# NRF52.net
KiCad netlist of a schematic drawn in Altium Designer
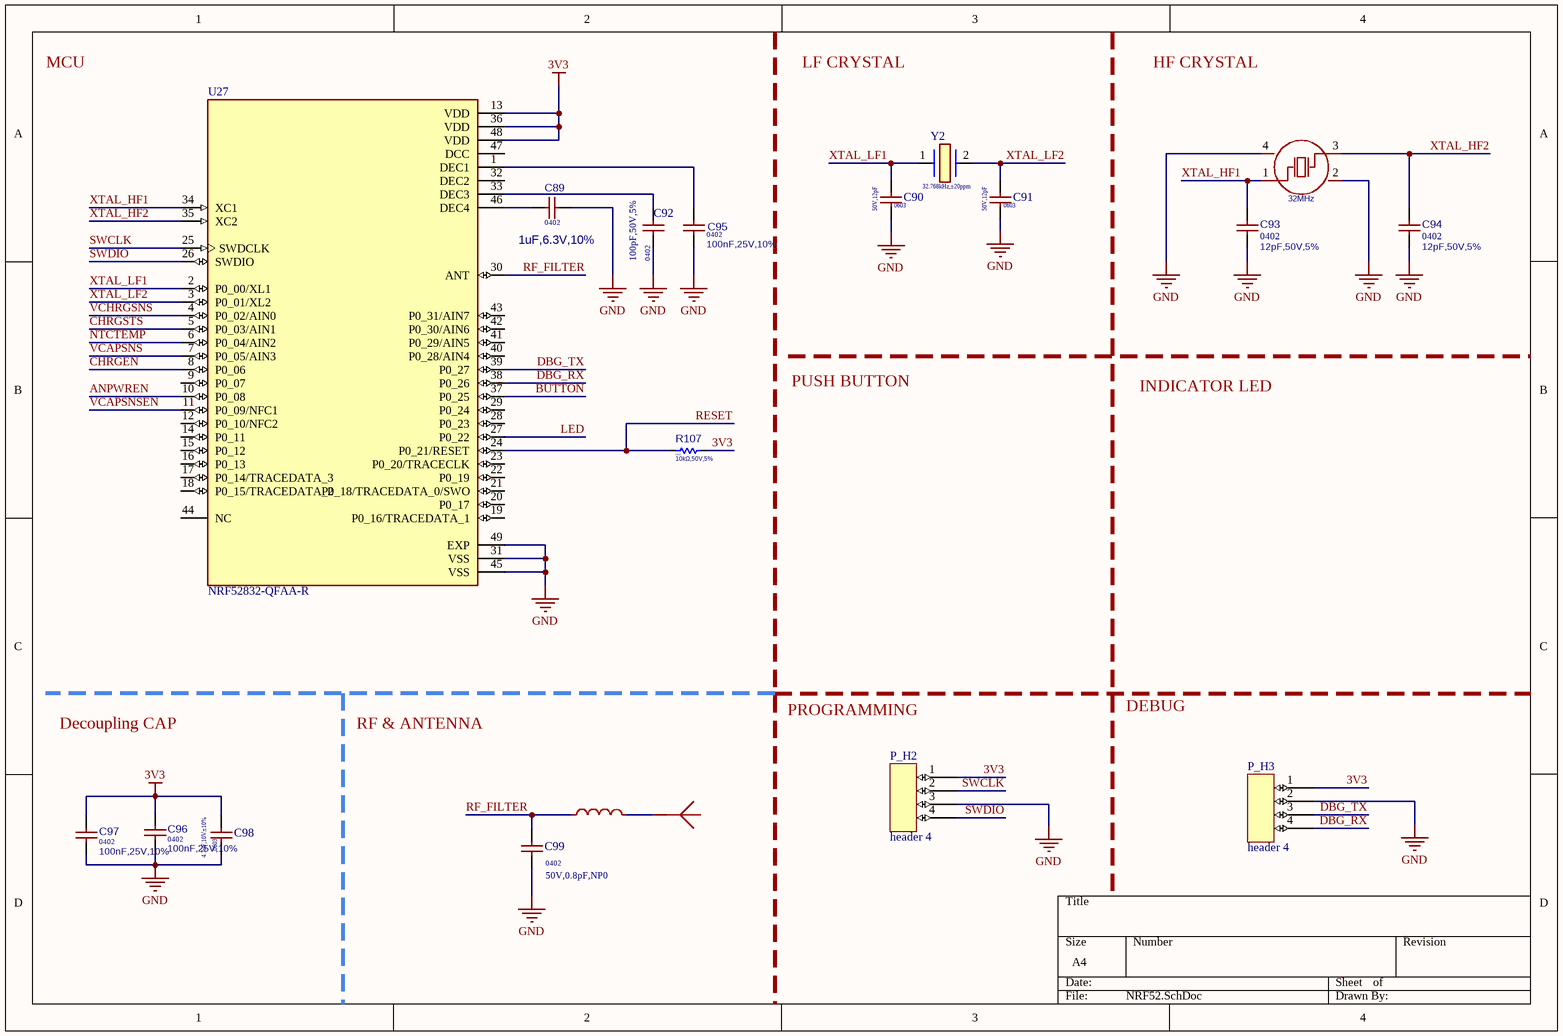
[diagram p0: NRF52.SchDoc]

(export (version "E")
  (design (tool "Eeschema 10.0.6"))
  (components
    (comp (ref "AE1")
      (value "2450AT18A100E")
      (footprint "ANT 1206")
      (description "0.5dBi 2.4G Antenna 2.4GHz 2W 1206 Antennas ROHS")
      (fields (field (name "MANUFACTURER") "JOHANSON"))
      (libsource (lib "RCL") (part "2450AT18A100E"))
    )
    (comp (ref "C89")
      (value "1uF,6.3V,10%")
      (footprint "C0402")
      (description "6.3V 1uF X7R ±10% 0402 Multilayer Ceramic Capacitors MLCC - SMD/SMT ROHS")
      (fields
        (field (name "MANUFACTURER") "YAGEO")
        (field (name "MPN") "CC0402KRX7R5BB105")
        (field (name "PACKAGE") "0402")
      )
      (libsource (lib "RCL") (part "CC0402KRX7R5BB105"))
    )
    (comp (ref "C90")
      (value "50V,12pF")
      (footprint "CAPC1608X90N")
      (description "50V 12pF C0G ±5% 0603 Multilayer Ceramic Capacitors MLCC - SMD/SMT ROHS")
      (fields
        (field (name "MANUFACTURER") "FH")
        (field (name "MPN") "0603CG120J500NT")
        (field (name "PACKAGE") "0603")
      )
      (libsource (lib "RCL") (part "0603CG120J500NT"))
    )
    (comp (ref "C91")
      (value "50V,12pF")
      (footprint "CAPC1608X90N")
      (description "50V 12pF C0G ±5% 0603 Multilayer Ceramic Capacitors MLCC - SMD/SMT ROHS")
      (fields
        (field (name "MANUFACTURER") "FH")
        (field (name "MPN") "0603CG120J500NT")
        (field (name "PACKAGE") "0603")
      )
      (libsource (lib "RCL") (part "0603CG120J500NT"))
    )
    (comp (ref "C92")
      (value "100pF,50V,5%")
      (footprint "C0402")
      (description "50V 100pF NP0 ±5% 0402 Multilayer Ceramic Capacitors MLCC - SMD/SMT ROHS")
      (fields
        (field (name "MANUFACTURER") "YAGEO")
        (field (name "MPN") "CC0402JRNPO9BN101")
        (field (name "PACKAGE") "0402")
      )
      (libsource (lib "RCL") (part "CC0402JRNPO9BN101"))
    )
    (comp (ref "C93")
      (value "12pF,50V,5%")
      (footprint "C0402")
      (description "12 pF ±5% 50V Ceramic Capacitor C0G, NP0 0402 (1005 Metric)")
      (fields
        (field (name "MANUFACTURER") "SAMSUNG")
        (field (name "MPN") "CL05C120JB51PNC")
        (field (name "PACKAGE") "0402")
      )
      (libsource (lib "RCL") (part "CL05C120JB51PNC"))
    )
    (comp (ref "C94")
      (value "12pF,50V,5%")
      (footprint "C0402")
      (description "12 pF ±5% 50V Ceramic Capacitor C0G, NP0 0402 (1005 Metric)")
      (fields
        (field (name "MANUFACTURER") "SAMSUNG")
        (field (name "MPN") "CL05C120JB51PNC")
        (field (name "PACKAGE") "0402")
      )
      (libsource (lib "RCL") (part "CL05C120JB51PNC"))
    )
    (comp (ref "C95")
      (value "100nF,25V,10%")
      (footprint "C0402")
      (description "25V 100nF X5R ±10% 0402 Multilayer Ceramic Capacitors MLCC - SMD/SMT ROHS")
      (fields
        (field (name "MANUFACTURER") "SAMSUNG")
        (field (name "MPN") "CL05A104KA5NNNC")
        (field (name "PACKAGE") "0402")
      )
      (libsource (lib "RCL") (part "CL05A104KA5NNNC"))
    )
    (comp (ref "C96")
      (value "100nF,25V,10%")
      (footprint "C0402")
      (description "25V 100nF X5R ±10% 0402 Multilayer Ceramic Capacitors MLCC - SMD/SMT ROHS")
      (fields
        (field (name "MANUFACTURER") "SAMSUNG")
        (field (name "MPN") "CL05A104KA5NNNC")
        (field (name "PACKAGE") "0402")
      )
      (libsource (lib "RCL") (part "CL05A104KA5NNNC"))
    )
    (comp (ref "C97")
      (value "100nF,25V,10%")
      (footprint "C0402")
      (description "25V 100nF X5R ±10% 0402 Multilayer Ceramic Capacitors MLCC - SMD/SMT ROHS")
      (fields
        (field (name "MANUFACTURER") "SAMSUNG")
        (field (name "MPN") "CL05A104KA5NNNC")
        (field (name "PACKAGE") "0402")
      )
      (libsource (lib "RCL") (part "CL05A104KA5NNNC"))
    )
    (comp (ref "C98")
      (value "4.7uF,10V±10%")
      (footprint "C0603")
      (description "10V 4.7uF X7R ±10% 0603 Multilayer Ceramic Capacitors MLCC - SMD/SMT ROHS")
      (fields
        (field (name "MPN") "CL10A475KQ8NNNC")
        (field (name "MANUFACTURER") "Samsung Electro-Mechanics")
        (field (name "PACKAGE") "0603")
      )
      (libsource (lib "RCL") (part "0603B475K100NT"))
    )
    (comp (ref "C99")
      (value "50V,0.8pF,NP0")
      (footprint "C0402")
      (description "50V 0.8pF NP0 0402 Multilayer Ceramic Capacitors MLCC - SMD/SMT ROHS")
      (fields
        (field (name "MANUFACTURER") "Walsin Tech Corp")
        (field (name "MPN") "RF15N0R8A500")
        (field (name "PACKAGE") "0402")
      )
      (libsource (lib "RCL") (part "RF15N0R8A500"))
    )
    (comp (ref "L4")
      (value "3.9nH")
      (footprint "L-0402")
      (description "300mA 3.9nH 200mΩ 0402 Inductors (SMD) ROHS")
      (fields (field (name "MANUFACTURER") "Sunlord") (field (name "MPN") "SDCL1005C3N9STDF"))
      (libsource (lib "RCL") (part "SDCL1005C3N9STDF"))
    )
    (comp (ref "P_H2")
      (value "header 4")
      (footprint "pin header 4")
      (description "Straight 2.54mm 6mm -40℃~+105℃ 1 3mm 4 2.54mm Black Brass 1x4P Straight,P=2.54mm Pin Headers ROHS")
      (libsource (lib "connector_button") (part "header 4"))
    )
    (comp (ref "P_H3")
      (value "header 4")
      (footprint "pin header 4")
      (description "Straight 2.54mm 6mm -40℃~+105℃ 1 3mm 4 2.54mm Black Brass 1x4P Straight,P=2.54mm Pin Headers ROHS")
      (libsource (lib "connector_button") (part "header 4"))
    )
    (comp (ref "R107")
      (value "10kΩ,50V,5%")
      (footprint "R0402")
      (description "62.5mW Thick Film Resistors 50V ±100ppm/℃ ±5% 10kΩ 0402 Chip Resistor - Surface Mount ROHS")
      (fields
        (field (name "MANUFACTURER") "YAGEO")
        (field (name "MPN") "RC0402JR-0710KL")
        (field (name "PACKAGE") "0402")
      )
      (libsource (lib "RCL") (part "RC0402JR-0710KL"))
    )
    (comp (ref "U27")
      (value "NRF52832-QFAA-R")
      (footprint "QFN40P600X600X90-49N")
      (description "IC RF TxRx + MCU Bluetooth, General ISM > 1GHz ANT, Bluetooth v5.0 2.4GHz 48-VFQFN Exposed Pad")
      (fields (field (name "MANUFACTURER") "Nordic"))
      (libsource (lib "IC") (part "NRF52832-QFAA-R"))
    )
    (comp (ref "X3")
      (value "32MHz")
      (footprint "SMD2016-4P,crystral")
      (description "32MHz,SMD2016-4P Crystals ROHS")
      (fields (field (name "MANUFACTURER") "HELE") (field (name "MPN") "X2C032000B81H-HS"))
      (libsource (lib "RCL") (part "X2C032000B81H-HS"))
    )
    (comp (ref "Y2")
      (value "32.768kHz,±20ppm")
      (footprint "SMD3215-2P")
      (description "32.768kHz SMD Crystal Resonator 12.5pF 70kΩ ±20ppm -40℃~+85℃ SMD3215-2P Crystals ROHS")
      (fields (field (name "MANUFACTURER") "Seiko Epson") (field (name "MPN") "Q13FC1350000400"))
      (libsource (lib "RCL") (part "Q13FC1350000400"))
    )
  )
  (nets
    (net (code "1") (name "/ANPWREN") (class "Default")
      (node (ref "U27") (pin "10") (pinfunction "P0_08_10") (pintype "bidirectional"))
    )
    (net (code "2") (name "/BUTTON") (class "Default")
      (node (ref "U27") (pin "37") (pinfunction "P0_25_37") (pintype "bidirectional"))
    )
    (net (code "3") (name "/CHRGEN") (class "Default")
      (node (ref "U27") (pin "8") (pinfunction "P0_06_8") (pintype "bidirectional"))
    )
    (net (code "4") (name "/CHRGSTS") (class "Default")
      (node (ref "U27") (pin "5") (pinfunction "P0_03/AIN1_5") (pintype "bidirectional"))
    )
    (net (code "5") (name "/DBG_RX") (class "Default")
      (node (ref "P_H3") (pin "4") (pintype "bidirectional"))
      (node (ref "U27") (pin "38") (pinfunction "P0_26_38") (pintype "bidirectional"))
    )
    (net (code "6") (name "/DBG_TX") (class "Default")
      (node (ref "P_H3") (pin "3") (pintype "bidirectional"))
      (node (ref "U27") (pin "39") (pinfunction "P0_27_39") (pintype "bidirectional"))
    )
    (net (code "7") (name "/LED") (class "Default")
      (node (ref "U27") (pin "27") (pinfunction "P0_22_27") (pintype "bidirectional"))
    )
    (net (code "8") (name "/NTCTEMP") (class "Default")
      (node (ref "U27") (pin "6") (pinfunction "P0_04/AIN2_6") (pintype "bidirectional"))
    )
    (net (code "9") (name "/RESET") (class "Default")
      (node (ref "R107") (pin "1") (pinfunction "1_1") (pintype "passive"))
      (node (ref "U27") (pin "24") (pinfunction "P0_21/RESET_24") (pintype "bidirectional"))
    )
    (net (code "10") (name "/RF_FILTER") (class "Default")
      (node (ref "C99") (pin "2") (pinfunction "2_2") (pintype "passive"))
      (node (ref "L4") (pin "1") (pinfunction "1_1") (pintype "passive"))
      (node (ref "U27") (pin "30") (pinfunction "ANT_30") (pintype "bidirectional"))
    )
    (net (code "11") (name "/SWCLK") (class "Default")
      (node (ref "P_H2") (pin "2") (pintype "bidirectional"))
      (node (ref "U27") (pin "25") (pinfunction "SWDCLK_25") (pintype "input"))
    )
    (net (code "12") (name "/SWDIO") (class "Default")
      (node (ref "P_H2") (pin "4") (pintype "bidirectional"))
      (node (ref "U27") (pin "26") (pinfunction "SWDIO_26") (pintype "bidirectional"))
    )
    (net (code "13") (name "/VCAPSNS") (class "Default")
      (node (ref "U27") (pin "7") (pinfunction "P0_05/AIN3_7") (pintype "bidirectional"))
    )
    (net (code "14") (name "/VCAPSNSEN") (class "Default")
      (node (ref "U27") (pin "11") (pinfunction "P0_09/NFC1_11") (pintype "bidirectional"))
    )
    (net (code "15") (name "/VCHRGSNS") (class "Default")
      (node (ref "U27") (pin "4") (pinfunction "P0_02/AIN0_4") (pintype "bidirectional"))
    )
    (net (code "16") (name "/XTAL_HF1") (class "Default")
      (node (ref "C93") (pin "2") (pinfunction "2_2") (pintype "passive"))
      (node (ref "U27") (pin "34") (pinfunction "XC1_34") (pintype "input"))
      (node (ref "X3") (pin "1") (pinfunction "OSC1_1") (pintype "passive"))
    )
    (net (code "17") (name "/XTAL_HF2") (class "Default")
      (node (ref "C94") (pin "2") (pinfunction "2_2") (pintype "passive"))
      (node (ref "U27") (pin "35") (pinfunction "XC2_35") (pintype "input"))
      (node (ref "X3") (pin "3") (pinfunction "OSC2_3") (pintype "passive"))
    )
    (net (code "18") (name "/XTAL_LF1") (class "Default")
      (node (ref "C90") (pin "2") (pinfunction "2_2") (pintype "passive"))
      (node (ref "U27") (pin "2") (pinfunction "P0_00/XL1_2") (pintype "bidirectional"))
      (node (ref "Y2") (pin "1") (pinfunction "CRYSTAL_2_1") (pintype "passive"))
    )
    (net (code "19") (name "/XTAL_LF2") (class "Default")
      (node (ref "C91") (pin "2") (pinfunction "2_2") (pintype "passive"))
      (node (ref "U27") (pin "3") (pinfunction "P0_01/XL2_3") (pintype "bidirectional"))
      (node (ref "Y2") (pin "2") (pintype "passive"))
    )
    (net (code "20") (name "3V3") (class "Default")
      (node (ref "C96") (pin "2") (pinfunction "2_2") (pintype "passive"))
      (node (ref "C97") (pin "2") (pinfunction "2_2") (pintype "passive"))
      (node (ref "C98") (pin "1") (pinfunction "1_1") (pintype "passive"))
      (node (ref "P_H2") (pin "1") (pintype "bidirectional"))
      (node (ref "P_H3") (pin "1") (pintype "bidirectional"))
      (node (ref "R107") (pin "2") (pinfunction "2_2") (pintype "passive"))
      (node (ref "U27") (pin "13") (pinfunction "VDD_13") (pintype "power_in"))
      (node (ref "U27") (pin "36") (pinfunction "VDD_36") (pintype "power_in"))
      (node (ref "U27") (pin "48") (pinfunction "VDD_48") (pintype "power_in"))
    )
    (net (code "21") (name "GND") (class "Default")
      (node (ref "C89") (pin "2") (pinfunction "2_2") (pintype "passive"))
      (node (ref "C90") (pin "1") (pinfunction "1_1") (pintype "passive"))
      (node (ref "C91") (pin "1") (pinfunction "1_1") (pintype "passive"))
      (node (ref "C92") (pin "1") (pinfunction "1_1") (pintype "passive"))
      (node (ref "C93") (pin "1") (pinfunction "1_1") (pintype "passive"))
      (node (ref "C94") (pin "1") (pinfunction "1_1") (pintype "passive"))
      (node (ref "C95") (pin "1") (pinfunction "1_1") (pintype "passive"))
      (node (ref "C96") (pin "1") (pinfunction "1_1") (pintype "passive"))
      (node (ref "C97") (pin "1") (pinfunction "1_1") (pintype "passive"))
      (node (ref "C98") (pin "2") (pinfunction "2_2") (pintype "passive"))
      (node (ref "C99") (pin "1") (pinfunction "1_1") (pintype "passive"))
      (node (ref "P_H2") (pin "3") (pintype "bidirectional"))
      (node (ref "P_H3") (pin "2") (pintype "bidirectional"))
      (node (ref "U27") (pin "31") (pinfunction "VSS_31") (pintype "power_in"))
      (node (ref "U27") (pin "45") (pinfunction "VSS_45") (pintype "power_in"))
      (node (ref "U27") (pin "49") (pinfunction "EXP_49") (pintype "power_in"))
      (node (ref "X3") (pin "2") (pinfunction "2_2") (pintype "passive"))
      (node (ref "X3") (pin "4") (pinfunction "4_4") (pintype "passive"))
    )
    (net (code "22") (name "Net-(AE1-ANT)") (class "Default")
      (node (ref "AE1") (pin "1") (pinfunction "ANT_1") (pintype "passive"))
      (node (ref "L4") (pin "2") (pinfunction "2_2") (pintype "passive"))
    )
    (net (code "23") (name "Net-(U27-DEC1)") (class "Default")
      (node (ref "C95") (pin "2") (pinfunction "2_2") (pintype "passive"))
      (node (ref "U27") (pin "1") (pinfunction "DEC1_1") (pintype "power_in"))
    )
    (net (code "24") (name "Net-(U27-DEC3)") (class "Default")
      (node (ref "C92") (pin "2") (pinfunction "2_2") (pintype "passive"))
      (node (ref "U27") (pin "33") (pinfunction "DEC3_33") (pintype "power_in"))
    )
    (net (code "25") (name "Net-(U27-DEC4)") (class "Default")
      (node (ref "C89") (pin "1") (pinfunction "1_1") (pintype "passive"))
      (node (ref "U27") (pin "46") (pinfunction "DEC4_46") (pintype "power_in"))
    )
    (net (code "26") (name "unconnected-(AE1-Pad2)") (class "Default")
      (node (ref "AE1") (pin "2") (pinfunction "2_2") (pintype "passive"))
    )
    (net (code "27") (name "unconnected-(U27-DCC-Pad47)") (class "Default")
      (node (ref "U27") (pin "47") (pinfunction "DCC_47") (pintype "power_in"))
    )
    (net (code "28") (name "unconnected-(U27-DEC2-Pad32)") (class "Default")
      (node (ref "U27") (pin "32") (pinfunction "DEC2_32") (pintype "power_in"))
    )
    (net (code "29") (name "unconnected-(U27-NC-Pad44)") (class "Default")
      (node (ref "U27") (pin "44") (pinfunction "NC_44") (pintype "passive"))
    )
    (net (code "30") (name "unconnected-(U27-P0_07-Pad9)") (class "Default")
      (node (ref "U27") (pin "9") (pinfunction "P0_07_9") (pintype "bidirectional"))
    )
    (net (code "31") (name "unconnected-(U27-P0_10{slash}NFC2-Pad12)") (class "Default")
      (node (ref "U27") (pin "12") (pinfunction "P0_10/NFC2_12") (pintype "bidirectional"))
    )
    (net (code "32") (name "unconnected-(U27-P0_11-Pad14)") (class "Default")
      (node (ref "U27") (pin "14") (pinfunction "P0_11_14") (pintype "bidirectional"))
    )
    (net (code "33") (name "unconnected-(U27-P0_12-Pad15)") (class "Default")
      (node (ref "U27") (pin "15") (pinfunction "P0_12_15") (pintype "bidirectional"))
    )
    (net (code "34") (name "unconnected-(U27-P0_13-Pad16)") (class "Default")
      (node (ref "U27") (pin "16") (pinfunction "P0_13_16") (pintype "bidirectional"))
    )
    (net (code "35") (name "unconnected-(U27-P0_14{slash}TRACEDATA_3-Pad17)") (class "Default")
      (node (ref "U27") (pin "17") (pinfunction "P0_14/TRACEDATA_3_17") (pintype "bidirectional"))
    )
    (net (code "36") (name "unconnected-(U27-P0_15{slash}TRACEDATA_2-Pad18)") (class "Default")
      (node (ref "U27") (pin "18") (pinfunction "P0_15/TRACEDATA_2_18") (pintype "bidirectional"))
    )
    (net (code "37") (name "unconnected-(U27-P0_16{slash}TRACEDATA_1-Pad19)") (class "Default")
      (node (ref "U27") (pin "19") (pinfunction "P0_16/TRACEDATA_1_19") (pintype "bidirectional"))
    )
    (net (code "38") (name "unconnected-(U27-P0_17-Pad20)") (class "Default")
      (node (ref "U27") (pin "20") (pinfunction "P0_17_20") (pintype "bidirectional"))
    )
    (net (code "39") (name "unconnected-(U27-P0_18{slash}TRACEDATA_0{slash}SWO-Pad21)") (class "Default")
      (node (ref "U27") (pin "21") (pinfunction "P0_18/TRACEDATA_0/SWO_21") (pintype "bidirectional"))
    )
    (net (code "40") (name "unconnected-(U27-P0_19-Pad22)") (class "Default")
      (node (ref "U27") (pin "22") (pinfunction "P0_19_22") (pintype "bidirectional"))
    )
    (net (code "41") (name "unconnected-(U27-P0_20{slash}TRACECLK-Pad23)") (class "Default")
      (node (ref "U27") (pin "23") (pinfunction "P0_20/TRACECLK_23") (pintype "bidirectional"))
    )
    (net (code "42") (name "unconnected-(U27-P0_23-Pad28)") (class "Default")
      (node (ref "U27") (pin "28") (pinfunction "P0_23_28") (pintype "bidirectional"))
    )
    (net (code "43") (name "unconnected-(U27-P0_24-Pad29)") (class "Default")
      (node (ref "U27") (pin "29") (pinfunction "P0_24_29") (pintype "bidirectional"))
    )
    (net (code "44") (name "unconnected-(U27-P0_28{slash}AIN4-Pad40)") (class "Default")
      (node (ref "U27") (pin "40") (pinfunction "P0_28/AIN4_40") (pintype "bidirectional"))
    )
    (net (code "45") (name "unconnected-(U27-P0_29{slash}AIN5-Pad41)") (class "Default")
      (node (ref "U27") (pin "41") (pinfunction "P0_29/AIN5_41") (pintype "bidirectional"))
    )
    (net (code "46") (name "unconnected-(U27-P0_30{slash}AIN6-Pad42)") (class "Default")
      (node (ref "U27") (pin "42") (pinfunction "P0_30/AIN6_42") (pintype "bidirectional"))
    )
    (net (code "47") (name "unconnected-(U27-P0_31{slash}AIN7-Pad43)") (class "Default")
      (node (ref "U27") (pin "43") (pinfunction "P0_31/AIN7_43") (pintype "bidirectional"))
    )
  )
)
